# TOP.net
KiCad netlist of a schematic drawn in Altium Designer
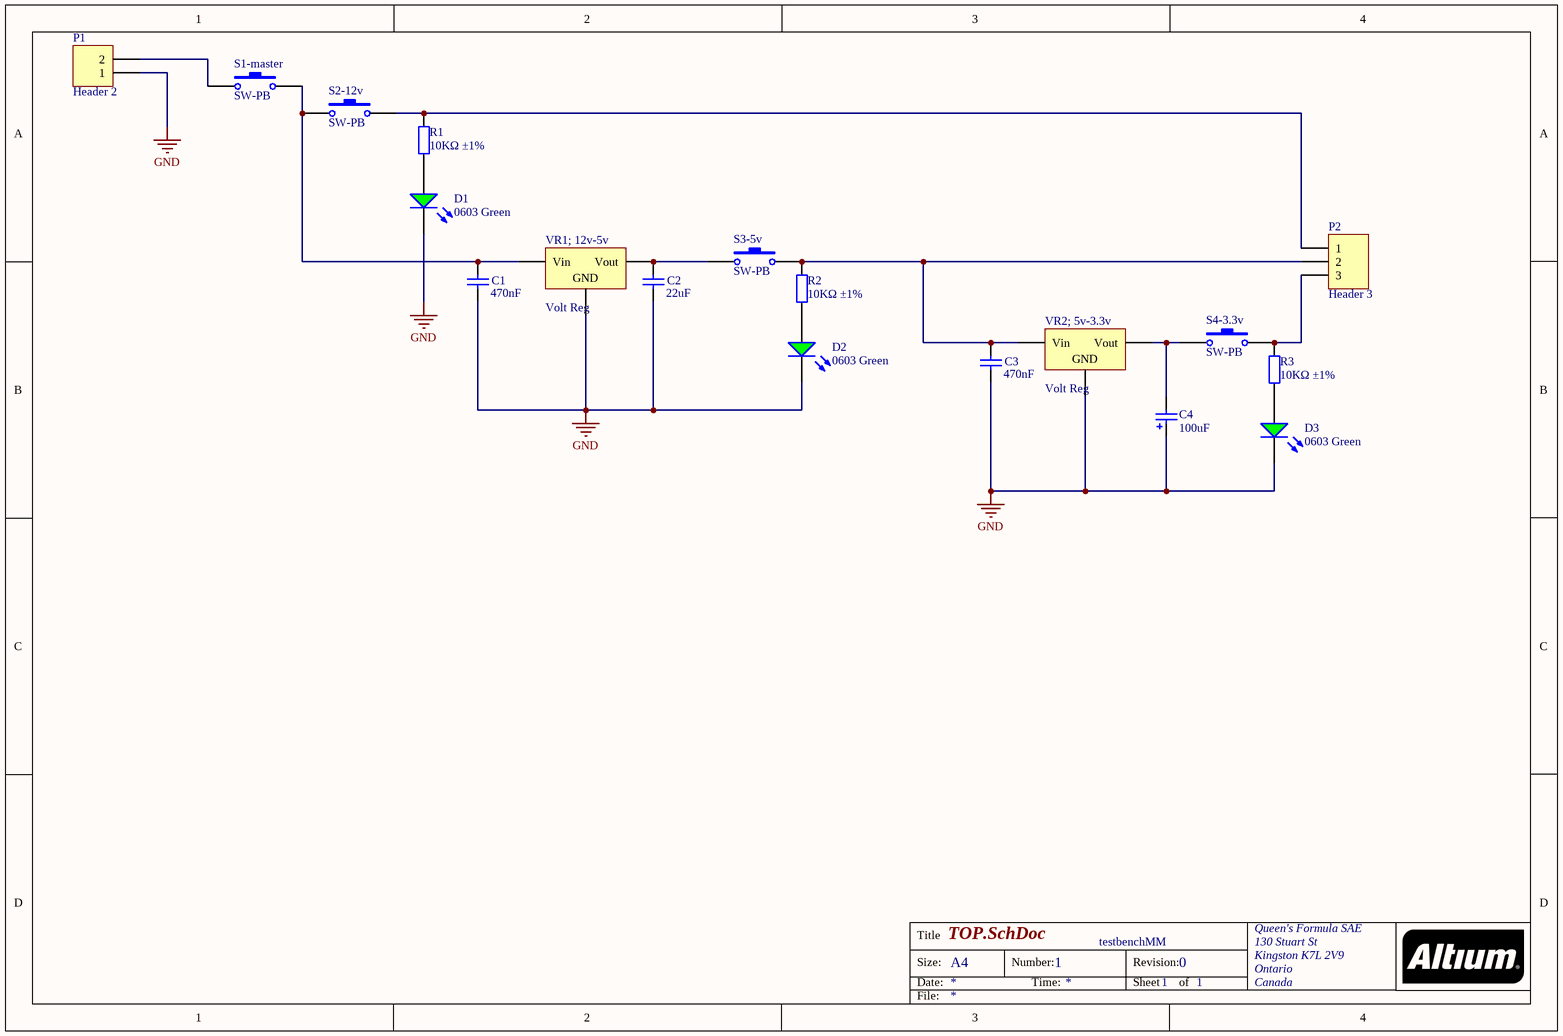
[diagram p0: TOP.SchDoc]

(export (version "E")
  (design (tool "Eeschema 10.0.6"))
  (components
    (comp (ref "C1")
      (value "470nF")
      (footprint "0805_C")
      (description "Chip capacitors")
      (fields
        (field (name "MANUFACTURER") "Samsung Electro-Mechanics")
        (field (name "PARTNUMBER") "CL21B474KBFNNNE")
      )
      (libsource (lib "Cap") (part "0805 470nF (474) 10% 50V"))
    )
    (comp (ref "C2")
      (value "22uF")
      (footprint "0805_C")
      (description "Chip capacitors")
      (fields
        (field (name "MANUFACTURER") "Samsung Electro-Mechanics")
        (field (name "PARTNUMBER") "CL21A226MAQNNNE")
      )
      (libsource (lib "Cap") (part "0805 22uF (226) 20% 25V"))
    )
    (comp (ref "C3")
      (value "470nF")
      (footprint "0805_C")
      (description "Chip capacitors")
      (fields
        (field (name "MANUFACTURER") "Samsung Electro-Mechanics")
        (field (name "PARTNUMBER") "CL21B474KBFNNNE")
      )
      (libsource (lib "Cap") (part "0805 470nF (474) 10% 50V"))
    )
    (comp (ref "C4")
      (value "100uF")
      (footprint "CASE-B_3528")
      (description "Tantalum capacitor")
      (fields (field (name "MANUFACTURER") "AVX") (field (name "PARTNUMBER") "TAJB107K006RNJ"))
      (libsource (lib "Cap") (part "3528 100uF (107) 10% 6.3V"))
    )
    (comp (ref "D1")
      (value "0603 Green")
      (footprint "0603_LED_S1")
      (description "LED")
      (libsource (lib "LED") (part "0603 LED Green"))
    )
    (comp (ref "D2")
      (value "0603 Green")
      (footprint "0603_LED_S1")
      (description "LED")
      (libsource (lib "LED") (part "0603 LED Green"))
    )
    (comp (ref "D3")
      (value "0603 Green")
      (footprint "0603_LED_S1")
      (description "LED")
      (libsource (lib "LED") (part "0603 LED Green"))
    )
    (comp (ref "P1")
      (value "Header 2")
      (footprint "HDR1X2")
      (description "Header, 2-Pin")
      (fields (field (name "PUBLISHER") "Altium Limited"))
      (libsource (lib "Miscellaneous Connectors") (part "Header 2"))
    )
    (comp (ref "P2")
      (value "Header 3")
      (footprint "HDR1X3")
      (description "Header, 3-Pin")
      (fields (field (name "PUBLISHER") "Altium Limited"))
      (libsource (lib "Miscellaneous Connectors") (part "Header 3"))
    )
    (comp (ref "R1")
      (value "10KΩ ±1%")
      (footprint "0603_R")
      (description "Chip resistor")
      (fields (field (name "MANUFACTURER") "Uniroyal Elec") (field (name "PARTNUMBER") "0603WAF1002T5E"))
      (libsource (lib "RES") (part "0603 10K (1002) 1%"))
    )
    (comp (ref "R2")
      (value "10KΩ ±1%")
      (footprint "0603_R")
      (description "Chip resistor")
      (fields (field (name "MANUFACTURER") "Uniroyal Elec") (field (name "PARTNUMBER") "0603WAF1002T5E"))
      (libsource (lib "RES") (part "0603 10K (1002) 1%"))
    )
    (comp (ref "R3")
      (value "10KΩ ±1%")
      (footprint "0603_R")
      (description "Chip resistor")
      (fields (field (name "MANUFACTURER") "Uniroyal Elec") (field (name "PARTNUMBER") "0603WAF1002T5E"))
      (libsource (lib "RES") (part "0603 10K (1002) 1%"))
    )
    (comp (ref "S1-master")
      (value "SW-PB")
      (footprint "SPST-2")
      (description "Switch")
      (fields (field (name "PUBLISHER") "Altium Limited"))
      (libsource (lib "Miscellaneous Devices") (part "SW-PB"))
    )
    (comp (ref "S2-12v")
      (value "SW-PB")
      (footprint "SPST-2")
      (description "Switch")
      (fields (field (name "PUBLISHER") "Altium Limited"))
      (libsource (lib "Miscellaneous Devices") (part "SW-PB"))
    )
    (comp (ref "S3-5v")
      (value "SW-PB")
      (footprint "SPST-2")
      (description "Switch")
      (fields (field (name "PUBLISHER") "Altium Limited"))
      (libsource (lib "Miscellaneous Devices") (part "SW-PB"))
    )
    (comp (ref "S4-3.3v")
      (value "SW-PB")
      (footprint "SPST-2")
      (description "Switch")
      (fields (field (name "PUBLISHER") "Altium Limited"))
      (libsource (lib "Miscellaneous Devices") (part "SW-PB"))
    )
    (comp (ref "VR1; 12v-5v")
      (value "Volt Reg")
      (footprint "D2PAK_N")
      (description "Voltage Regulator")
      (fields (field (name "PUBLISHER") "Altium Limited"))
      (libsource (lib "Miscellaneous Devices") (part "Volt Reg"))
    )
    (comp (ref "VR2; 5v-3.3v")
      (value "Volt Reg")
      (footprint "D2PAK_N")
      (description "Voltage Regulator")
      (fields (field (name "PUBLISHER") "Altium Limited"))
      (libsource (lib "Miscellaneous Devices") (part "Volt Reg"))
    )
  )
  (nets
    (net (code "1") (name "GND") (class "Default")
      (node (ref "C1") (pin "2") (pinfunction "2_2") (pintype "passive"))
      (node (ref "C2") (pin "1") (pinfunction "1_1") (pintype "passive"))
      (node (ref "C3") (pin "2") (pinfunction "2_2") (pintype "passive"))
      (node (ref "C4") (pin "1") (pinfunction "1_1") (pintype "passive"))
      (node (ref "D1") (pin "K") (pinfunction "K_K") (pintype "passive"))
      (node (ref "D2") (pin "K") (pinfunction "K_K") (pintype "passive"))
      (node (ref "D3") (pin "K") (pinfunction "K_K") (pintype "passive"))
      (node (ref "P1") (pin "1") (pinfunction "1_1") (pintype "passive"))
      (node (ref "VR1; 12v-5v") (pin "2") (pinfunction "GND_2") (pintype "passive"))
      (node (ref "VR2; 5v-3.3v") (pin "2") (pinfunction "GND_2") (pintype "passive"))
    )
    (net (code "2") (name "Net-(D1-PadA)") (class "Default")
      (node (ref "D1") (pin "A") (pinfunction "A_A") (pintype "passive"))
      (node (ref "R1") (pin "1") (pinfunction "1_1") (pintype "passive"))
    )
    (net (code "3") (name "Net-(D2-PadA)") (class "Default")
      (node (ref "D2") (pin "A") (pinfunction "A_A") (pintype "passive"))
      (node (ref "R2") (pin "1") (pinfunction "1_1") (pintype "passive"))
    )
    (net (code "4") (name "Net-(D3-PadA)") (class "Default")
      (node (ref "D3") (pin "A") (pinfunction "A_A") (pintype "passive"))
      (node (ref "R3") (pin "1") (pinfunction "1_1") (pintype "passive"))
    )
    (net (code "5") (name "Net-(P1-Pad2)") (class "Default")
      (node (ref "P1") (pin "2") (pinfunction "2_2") (pintype "passive"))
      (node (ref "S1-master") (pin "1") (pinfunction "1_1") (pintype "passive"))
    )
    (net (code "6") (name "Net-(P2-Pad1)") (class "Default")
      (node (ref "P2") (pin "1") (pinfunction "1_1") (pintype "passive"))
      (node (ref "R1") (pin "2") (pinfunction "2_2") (pintype "passive"))
      (node (ref "S2-12v") (pin "2") (pinfunction "2_2") (pintype "passive"))
    )
    (net (code "7") (name "Net-(P2-Pad3)") (class "Default")
      (node (ref "P2") (pin "3") (pinfunction "3_3") (pintype "passive"))
      (node (ref "R3") (pin "2") (pinfunction "2_2") (pintype "passive"))
      (node (ref "S4-3.3v") (pin "2") (pinfunction "2_2") (pintype "passive"))
    )
    (net (code "8") (name "Net-(VR1; 12v-5v-Vin)") (class "Default")
      (node (ref "C1") (pin "1") (pinfunction "1_1") (pintype "passive"))
      (node (ref "S1-master") (pin "2") (pinfunction "2_2") (pintype "passive"))
      (node (ref "S2-12v") (pin "1") (pinfunction "1_1") (pintype "passive"))
      (node (ref "VR1; 12v-5v") (pin "1") (pinfunction "Vin_1") (pintype "passive"))
    )
    (net (code "9") (name "Net-(VR1; 12v-5v-Vout)") (class "Default")
      (node (ref "C2") (pin "2") (pinfunction "2_2") (pintype "passive"))
      (node (ref "S3-5v") (pin "1") (pinfunction "1_1") (pintype "passive"))
      (node (ref "VR1; 12v-5v") (pin "3") (pinfunction "Vout_3") (pintype "passive"))
    )
    (net (code "10") (name "Net-(VR2; 5v-3.3v-Vin)") (class "Default")
      (node (ref "C3") (pin "1") (pinfunction "1_1") (pintype "passive"))
      (node (ref "P2") (pin "2") (pinfunction "2_2") (pintype "passive"))
      (node (ref "R2") (pin "2") (pinfunction "2_2") (pintype "passive"))
      (node (ref "S3-5v") (pin "2") (pinfunction "2_2") (pintype "passive"))
      (node (ref "VR2; 5v-3.3v") (pin "1") (pinfunction "Vin_1") (pintype "passive"))
    )
    (net (code "11") (name "Net-(VR2; 5v-3.3v-Vout)") (class "Default")
      (node (ref "C4") (pin "2") (pinfunction "2_2") (pintype "passive"))
      (node (ref "S4-3.3v") (pin "1") (pinfunction "1_1") (pintype "passive"))
      (node (ref "VR2; 5v-3.3v") (pin "3") (pinfunction "Vout_3") (pintype "passive"))
    )
  )
)
